# BiphasicBoard.net
KiCad netlist of a schematic drawn in EAGLE
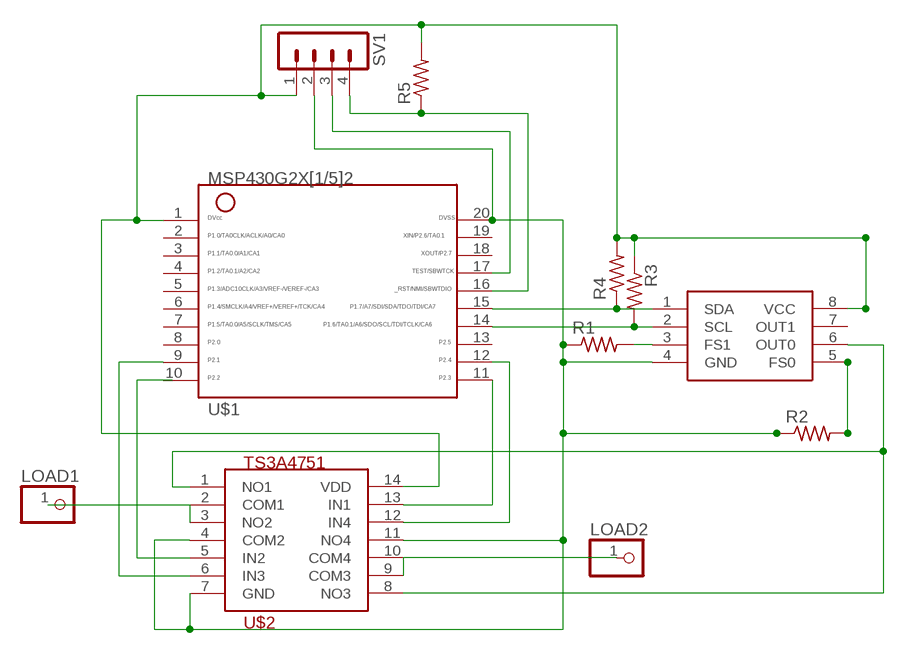
[diagram p0: schematic, sheet 1]

(export (version "E")
  (design (tool "Eeschema 10.0.6"))
  (components
    (comp (ref "LOAD1")
      (value "PINHD-1X1")
      (footprint "eagle-import:1X01")
      (libsource (lib "eagle-import") (part "PINHD-1X1"))
    )
    (comp (ref "LOAD2")
      (value "PINHD-1X1")
      (footprint "eagle-import:1X01")
      (libsource (lib "eagle-import") (part "PINHD-1X1"))
    )
    (comp (ref "R1")
      (value "R-US_R0603")
      (footprint "eagle-import:R0603")
      (libsource (lib "eagle-import") (part "R-US_R0603"))
    )
    (comp (ref "R2")
      (value "R-US_R0603")
      (footprint "eagle-import:R0603")
      (libsource (lib "eagle-import") (part "R-US_R0603"))
    )
    (comp (ref "R3")
      (value "R-US_R0603")
      (footprint "eagle-import:R0603")
      (libsource (lib "eagle-import") (part "R-US_R0603"))
    )
    (comp (ref "R4")
      (value "R-US_R0603")
      (footprint "eagle-import:R0603")
      (libsource (lib "eagle-import") (part "R-US_R0603"))
    )
    (comp (ref "R5")
      (value "R-US_R0603")
      (footprint "eagle-import:R0603")
      (libsource (lib "eagle-import") (part "R-US_R0603"))
    )
    (comp (ref "SV1")
      (value "MA04-1")
      (footprint "eagle-import:MA04-1")
      (libsource (lib "eagle-import") (part "MA04-1"))
    )
    (comp (ref "U$1")
      (value "G2X[1/5]2---PW20")
      (footprint "eagle-import:PW20")
      (libsource (lib "eagle-import") (part "G2X[1/5]2---PW20"))
    )
    (comp (ref "U$2")
      (value "TS3A4751")
      (footprint "eagle-import:TS3A4751#2")
      (libsource (lib "eagle-import") (part "TS3A4751"))
    )
    (comp (ref "U$3")
      (value "DS4432U+")
      (footprint "eagle-import:DS4432U+")
      (libsource (lib "eagle-import") (part "DS4432U+"))
    )
  )
  (nets
    (net (code "1") (name "Net-(R5-Pad1)") (class "Default")
      (node (ref "R5") (pin "1") (pinfunction "1_1") (pintype "passive"))
      (node (ref "SV1") (pin "4") (pinfunction "4_4") (pintype "passive"))
      (node (ref "U$1") (pin "16") (pinfunction "16_16") (pintype "bidirectional"))
    )
    (net (code "2") (name "Net-(SV1-Pad3)") (class "Default")
      (node (ref "SV1") (pin "3") (pinfunction "3_3") (pintype "passive"))
      (node (ref "U$1") (pin "17") (pinfunction "17_17") (pintype "bidirectional"))
    )
    (net (code "3") (name "Net-(U$2-COM1)") (class "Default")
      (node (ref "LOAD1") (pin "1") (pinfunction "1_1") (pintype "passive"))
      (node (ref "U$2") (pin "2") (pinfunction "COM1_2") (pintype "bidirectional"))
      (node (ref "U$2") (pin "3") (pinfunction "NO2_3") (pintype "bidirectional"))
    )
    (net (code "4") (name "Net-(U$2-COM2)") (class "Default")
      (node (ref "R1") (pin "1") (pinfunction "1_1") (pintype "passive"))
      (node (ref "R2") (pin "1") (pinfunction "1_1") (pintype "passive"))
      (node (ref "SV1") (pin "2") (pinfunction "2_2") (pintype "passive"))
      (node (ref "U$1") (pin "20") (pinfunction "20_20") (pintype "bidirectional"))
      (node (ref "U$2") (pin "11") (pinfunction "NO4_11") (pintype "bidirectional"))
      (node (ref "U$2") (pin "4") (pinfunction "COM2_4") (pintype "bidirectional"))
      (node (ref "U$2") (pin "7") (pinfunction "GND_7") (pintype "bidirectional"))
      (node (ref "U$3") (pin "4") (pinfunction "GND_4") (pintype "bidirectional"))
    )
    (net (code "5") (name "Net-(U$2-COM3)") (class "Default")
      (node (ref "LOAD2") (pin "1") (pinfunction "1_1") (pintype "passive"))
      (node (ref "U$2") (pin "10") (pinfunction "COM4_10") (pintype "bidirectional"))
      (node (ref "U$2") (pin "9") (pinfunction "COM3_9") (pintype "bidirectional"))
    )
    (net (code "6") (name "Net-(U$2-IN1)") (class "Default")
      (node (ref "U$1") (pin "11") (pinfunction "11_11") (pintype "bidirectional"))
      (node (ref "U$2") (pin "13") (pinfunction "IN1_13") (pintype "bidirectional"))
    )
    (net (code "7") (name "Net-(U$2-IN2)") (class "Default")
      (node (ref "U$1") (pin "10") (pinfunction "10_10") (pintype "bidirectional"))
      (node (ref "U$2") (pin "5") (pinfunction "IN2_5") (pintype "bidirectional"))
    )
    (net (code "8") (name "Net-(U$2-IN3)") (class "Default")
      (node (ref "U$1") (pin "9") (pinfunction "9_9") (pintype "bidirectional"))
      (node (ref "U$2") (pin "6") (pinfunction "IN3_6") (pintype "bidirectional"))
    )
    (net (code "9") (name "Net-(U$2-IN4)") (class "Default")
      (node (ref "U$1") (pin "12") (pinfunction "12_12") (pintype "bidirectional"))
      (node (ref "U$2") (pin "12") (pinfunction "IN4_12") (pintype "bidirectional"))
    )
    (net (code "10") (name "Net-(U$2-NO1)") (class "Default")
      (node (ref "U$2") (pin "1") (pinfunction "NO1_1") (pintype "bidirectional"))
      (node (ref "U$2") (pin "8") (pinfunction "NO3_8") (pintype "bidirectional"))
      (node (ref "U$3") (pin "6") (pinfunction "OUT0_6") (pintype "bidirectional"))
    )
    (net (code "11") (name "Net-(U$2-VDD)") (class "Default")
      (node (ref "R3") (pin "1") (pinfunction "1_1") (pintype "passive"))
      (node (ref "R4") (pin "2") (pinfunction "2_2") (pintype "passive"))
      (node (ref "R5") (pin "2") (pinfunction "2_2") (pintype "passive"))
      (node (ref "SV1") (pin "1") (pinfunction "1_1") (pintype "passive"))
      (node (ref "U$1") (pin "1") (pinfunction "1_1") (pintype "bidirectional"))
      (node (ref "U$2") (pin "14") (pinfunction "VDD_14") (pintype "bidirectional"))
      (node (ref "U$3") (pin "8") (pinfunction "VCC_8") (pintype "bidirectional"))
    )
    (net (code "12") (name "Net-(U$3-FS0)") (class "Default")
      (node (ref "R2") (pin "2") (pinfunction "2_2") (pintype "passive"))
      (node (ref "U$3") (pin "5") (pinfunction "FS0_5") (pintype "bidirectional"))
    )
    (net (code "13") (name "Net-(U$3-FS1)") (class "Default")
      (node (ref "R1") (pin "2") (pinfunction "2_2") (pintype "passive"))
      (node (ref "U$3") (pin "3") (pinfunction "FS1_3") (pintype "bidirectional"))
    )
    (net (code "14") (name "Net-(U$3-SCL)") (class "Default")
      (node (ref "R3") (pin "2") (pinfunction "2_2") (pintype "passive"))
      (node (ref "U$1") (pin "14") (pinfunction "14_14") (pintype "bidirectional"))
      (node (ref "U$3") (pin "2") (pinfunction "SCL_2") (pintype "bidirectional"))
    )
    (net (code "15") (name "Net-(U$3-SDA)") (class "Default")
      (node (ref "R4") (pin "1") (pinfunction "1_1") (pintype "passive"))
      (node (ref "U$1") (pin "15") (pinfunction "15_15") (pintype "bidirectional"))
      (node (ref "U$3") (pin "1") (pinfunction "SDA_1") (pintype "bidirectional"))
    )
    (net (code "16") (name "unconnected-(U$1-Pad2)") (class "Default")
      (node (ref "U$1") (pin "2") (pinfunction "2_2") (pintype "bidirectional"))
    )
    (net (code "17") (name "unconnected-(U$1-Pad3)") (class "Default")
      (node (ref "U$1") (pin "3") (pinfunction "3_3") (pintype "bidirectional"))
    )
    (net (code "18") (name "unconnected-(U$1-Pad4)") (class "Default")
      (node (ref "U$1") (pin "4") (pinfunction "4_4") (pintype "bidirectional"))
    )
    (net (code "19") (name "unconnected-(U$1-Pad5)") (class "Default")
      (node (ref "U$1") (pin "5") (pinfunction "5_5") (pintype "bidirectional"))
    )
    (net (code "20") (name "unconnected-(U$1-Pad6)") (class "Default")
      (node (ref "U$1") (pin "6") (pinfunction "6_6") (pintype "bidirectional"))
    )
    (net (code "21") (name "unconnected-(U$1-Pad7)") (class "Default")
      (node (ref "U$1") (pin "7") (pinfunction "7_7") (pintype "bidirectional"))
    )
    (net (code "22") (name "unconnected-(U$1-Pad8)") (class "Default")
      (node (ref "U$1") (pin "8") (pinfunction "8_8") (pintype "bidirectional"))
    )
    (net (code "23") (name "unconnected-(U$1-Pad13)") (class "Default")
      (node (ref "U$1") (pin "13") (pinfunction "13_13") (pintype "bidirectional"))
    )
    (net (code "24") (name "unconnected-(U$1-Pad18)") (class "Default")
      (node (ref "U$1") (pin "18") (pinfunction "18_18") (pintype "bidirectional"))
    )
    (net (code "25") (name "unconnected-(U$1-Pad19)") (class "Default")
      (node (ref "U$1") (pin "19") (pinfunction "19_19") (pintype "bidirectional"))
    )
    (net (code "26") (name "unconnected-(U$3-OUT1-Pad7)") (class "Default")
      (node (ref "U$3") (pin "7") (pinfunction "OUT1_7") (pintype "bidirectional"))
    )
  )
)
